# sml-lx0404-breakout.net
KiCad netlist of a schematic drawn in EAGLE
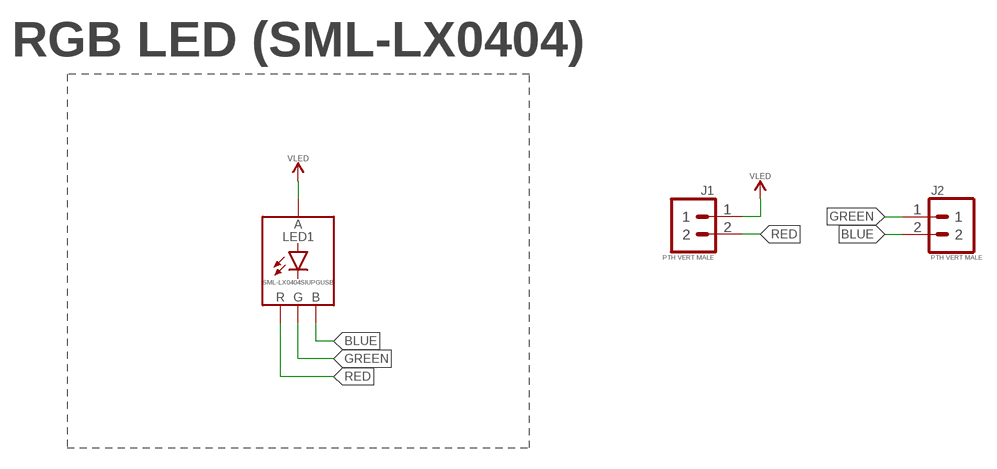
[diagram p0: schematic, sheet 1]

(export (version "E")
  (design (tool "Eeschema 10.0.6"))
  (components
    (comp (ref "J1")
      (value "PTH VERT MALE")
      (footprint "eagle-import:HDRV2W64P254_1X2_508X254X838B")
      (fields (field (name "MFR") "Sullins Connector Solutions") (field (name "MPN") "PEC02SAAN"))
      (libsource (lib "eagle-import") (part "1X02_PTH_VERT_MALE_2.54MM"))
    )
    (comp (ref "J2")
      (value "PTH VERT MALE")
      (footprint "eagle-import:HDRV2W64P254_1X2_508X254X838B")
      (fields (field (name "MFR") "Sullins Connector Solutions") (field (name "MPN") "PEC02SAAN"))
      (libsource (lib "eagle-import") (part "1X02_PTH_VERT_MALE_2.54MM"))
    )
    (comp (ref "LED1")
      (value "SML-LX0404SIUPGUSB")
      (footprint "eagle-import:DIODFN100X100X30-4N")
      (fields (field (name "MFR") "Lumex Opto/Components Inc."))
      (libsource (lib "eagle-import") (part "SML-LX0404SIUPGUSB"))
    )
  )
  (nets
    (net (code "1") (name "BLUE") (class "Default")
      (node (ref "J2") (pin "2") (pinfunction "2_2") (pintype "passive"))
      (node (ref "LED1") (pin "3") (pinfunction "B_3") (pintype "bidirectional"))
    )
    (net (code "2") (name "GREEN") (class "Default")
      (node (ref "J2") (pin "1") (pinfunction "1_1") (pintype "passive"))
      (node (ref "LED1") (pin "4") (pinfunction "G_4") (pintype "bidirectional"))
    )
    (net (code "3") (name "RED") (class "Default")
      (node (ref "J1") (pin "2") (pinfunction "2_2") (pintype "passive"))
      (node (ref "LED1") (pin "2") (pinfunction "R_2") (pintype "bidirectional"))
    )
    (net (code "4") (name "VLED") (class "Default")
      (node (ref "J1") (pin "1") (pinfunction "1_1") (pintype "passive"))
      (node (ref "LED1") (pin "1") (pinfunction "A_1") (pintype "bidirectional"))
    )
  )
)
